# BRAIN.net
KiCad netlist of a schematic drawn in EAGLE
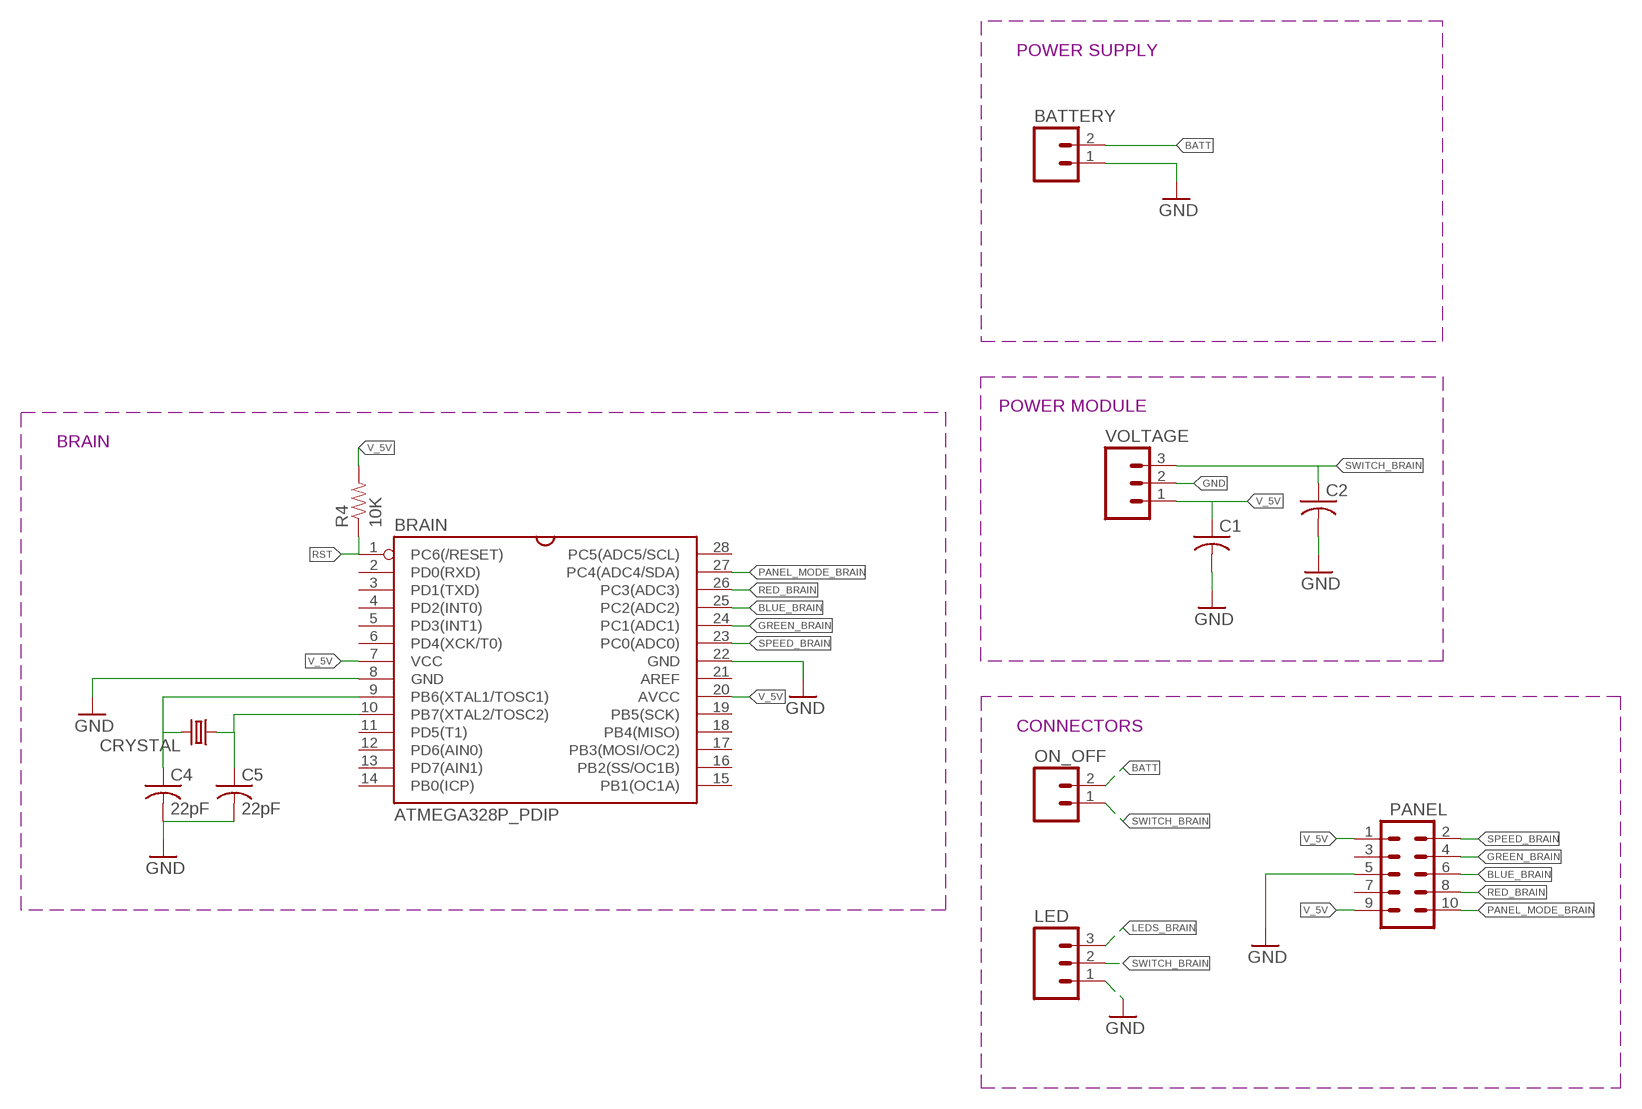
[diagram p0: schematic, sheet 1]

(export (version "E")
  (design (tool "Eeschema 10.0.6"))
  (components
    (comp (ref "BATTERY")
      (value "M02PTH")
      (footprint "eagle-import:1X02")
      (libsource (lib "eagle-import") (part "M02PTH"))
    )
    (comp (ref "BRAIN")
      (value "ATMEGA328P_PDIP")
      (footprint "eagle-import:DIL-28-3")
      (libsource (lib "eagle-import") (part "ATMEGA328P_PDIP"))
    )
    (comp (ref "C1")
      (value "C-US025-025X050")
      (footprint "eagle-import:C025-025X050")
      (libsource (lib "eagle-import") (part "C-US025-025X050"))
    )
    (comp (ref "C2")
      (value "C-US025-025X050")
      (footprint "eagle-import:C025-025X050")
      (libsource (lib "eagle-import") (part "C-US025-025X050"))
    )
    (comp (ref "C4")
      (value "22pF")
      (footprint "eagle-import:C025-024X044")
      (libsource (lib "eagle-import") (part "C-US025-024X044"))
    )
    (comp (ref "C5")
      (value "22pF")
      (footprint "eagle-import:C025-024X044")
      (libsource (lib "eagle-import") (part "C-US025-024X044"))
    )
    (comp (ref "CRYSTAL")
      (value "CRYSTALHC49US")
      (footprint "eagle-import:HC49US")
      (libsource (lib "eagle-import") (part "CRYSTALHC49US"))
    )
    (comp (ref "LED")
      (value "M03JST-PTH")
      (footprint "eagle-import:JST-3-PTH")
      (libsource (lib "eagle-import") (part "M03JST-PTH"))
    )
    (comp (ref "ON_OFF")
      (value "M02-JST-2-PTH-NO_SILK")
      (footprint "eagle-import:JST-2-PTH-NS")
      (libsource (lib "eagle-import") (part "M02-JST-2-PTH-NO_SILK"))
    )
    (comp (ref "PANEL")
      (value "M05X2SHD")
      (footprint "eagle-import:2X5-SHROUDED")
      (libsource (lib "eagle-import") (part "M05X2SHD"))
    )
    (comp (ref "R4")
      (value "10K")
      (footprint "eagle-import:1206")
      (libsource (lib "eagle-import") (part "RESISTOR1206"))
    )
    (comp (ref "VOLTAGE")
      (value "M03PTH")
      (footprint "eagle-import:1X03")
      (libsource (lib "eagle-import") (part "M03PTH"))
    )
  )
  (nets
    (net (code "1") (name "BATT") (class "Default")
      (node (ref "BATTERY") (pin "2") (pinfunction "2_2") (pintype "passive"))
      (node (ref "ON_OFF") (pin "2") (pinfunction "2_2") (pintype "passive"))
    )
    (net (code "2") (name "BLUE_BRAIN") (class "Default")
      (node (ref "BRAIN") (pin "25") (pinfunction "PC2(ADC2)_25") (pintype "bidirectional"))
      (node (ref "PANEL") (pin "6") (pinfunction "6_6") (pintype "passive"))
    )
    (net (code "3") (name "GND") (class "Default")
      (node (ref "BATTERY") (pin "1") (pinfunction "1_1") (pintype "passive"))
      (node (ref "BRAIN") (pin "22") (pinfunction "GND_22") (pintype "bidirectional"))
      (node (ref "BRAIN") (pin "8") (pinfunction "GND_8") (pintype "bidirectional"))
      (node (ref "C1") (pin "2") (pinfunction "2_2") (pintype "passive"))
      (node (ref "C2") (pin "2") (pinfunction "2_2") (pintype "passive"))
      (node (ref "C4") (pin "2") (pinfunction "2_2") (pintype "passive"))
      (node (ref "C5") (pin "2") (pinfunction "2_2") (pintype "passive"))
      (node (ref "LED") (pin "1") (pinfunction "1_1") (pintype "passive"))
      (node (ref "PANEL") (pin "5") (pinfunction "5_5") (pintype "passive"))
      (node (ref "VOLTAGE") (pin "2") (pinfunction "2_2") (pintype "passive"))
    )
    (net (code "4") (name "GREEN_BRAIN") (class "Default")
      (node (ref "BRAIN") (pin "24") (pinfunction "PC1(ADC1)_24") (pintype "bidirectional"))
      (node (ref "PANEL") (pin "4") (pinfunction "4_4") (pintype "passive"))
    )
    (net (code "5") (name "LEDS_BRAIN") (class "Default")
      (node (ref "LED") (pin "3") (pinfunction "3_3") (pintype "passive"))
    )
    (net (code "6") (name "Net-(BRAIN-PB6(XTAL1{slash}TOSC1))") (class "Default")
      (node (ref "BRAIN") (pin "9") (pinfunction "PB6(XTAL1/TOSC1)_9") (pintype "bidirectional"))
      (node (ref "C4") (pin "1") (pinfunction "1_1") (pintype "passive"))
      (node (ref "CRYSTAL") (pin "2") (pinfunction "2_2") (pintype "passive"))
    )
    (net (code "7") (name "Net-(BRAIN-PB7(XTAL2{slash}TOSC2))") (class "Default")
      (node (ref "BRAIN") (pin "10") (pinfunction "PB7(XTAL2/TOSC2)_10") (pintype "bidirectional"))
      (node (ref "C5") (pin "1") (pinfunction "1_1") (pintype "passive"))
      (node (ref "CRYSTAL") (pin "1") (pinfunction "1_1") (pintype "passive"))
    )
    (net (code "8") (name "PANEL_MODE_BRAIN") (class "Default")
      (node (ref "BRAIN") (pin "27") (pinfunction "PC4(ADC4/SDA)_27") (pintype "bidirectional"))
      (node (ref "PANEL") (pin "10") (pinfunction "10_10") (pintype "passive"))
    )
    (net (code "9") (name "RED_BRAIN") (class "Default")
      (node (ref "BRAIN") (pin "26") (pinfunction "PC3(ADC3)_26") (pintype "bidirectional"))
      (node (ref "PANEL") (pin "8") (pinfunction "8_8") (pintype "passive"))
    )
    (net (code "10") (name "RST") (class "Default")
      (node (ref "BRAIN") (pin "1") (pinfunction "PC6(/RESET)_1") (pintype "bidirectional"))
      (node (ref "R4") (pin "1") (pinfunction "1_1") (pintype "passive"))
    )
    (net (code "11") (name "SPEED_BRAIN") (class "Default")
      (node (ref "BRAIN") (pin "23") (pinfunction "PC0(ADC0)_23") (pintype "bidirectional"))
      (node (ref "PANEL") (pin "2") (pinfunction "2_2") (pintype "passive"))
    )
    (net (code "12") (name "SWITCH_BRAIN") (class "Default")
      (node (ref "C2") (pin "1") (pinfunction "1_1") (pintype "passive"))
      (node (ref "LED") (pin "2") (pinfunction "2_2") (pintype "passive"))
      (node (ref "ON_OFF") (pin "1") (pinfunction "1_1") (pintype "passive"))
      (node (ref "VOLTAGE") (pin "3") (pinfunction "3_3") (pintype "passive"))
    )
    (net (code "13") (name "V_5V") (class "Default")
      (node (ref "BRAIN") (pin "20") (pinfunction "AVCC_20") (pintype "bidirectional"))
      (node (ref "BRAIN") (pin "7") (pinfunction "VCC_7") (pintype "bidirectional"))
      (node (ref "C1") (pin "1") (pinfunction "1_1") (pintype "passive"))
      (node (ref "PANEL") (pin "1") (pinfunction "1_1") (pintype "passive"))
      (node (ref "PANEL") (pin "9") (pinfunction "9_9") (pintype "passive"))
      (node (ref "R4") (pin "2") (pinfunction "2_2") (pintype "passive"))
      (node (ref "VOLTAGE") (pin "1") (pinfunction "1_1") (pintype "passive"))
    )
    (net (code "14") (name "unconnected-(BRAIN-AREF-Pad21)") (class "Default")
      (node (ref "BRAIN") (pin "21") (pinfunction "AREF_21") (pintype "bidirectional"))
    )
    (net (code "15") (name "unconnected-(BRAIN-PB0(ICP)-Pad14)") (class "Default")
      (node (ref "BRAIN") (pin "14") (pinfunction "PB0(ICP)_14") (pintype "bidirectional"))
    )
    (net (code "16") (name "unconnected-(BRAIN-PB1(OC1A)-Pad15)") (class "Default")
      (node (ref "BRAIN") (pin "15") (pinfunction "PB1(OC1A)_15") (pintype "bidirectional"))
    )
    (net (code "17") (name "unconnected-(BRAIN-PB2(SS{slash}OC1B)-Pad16)") (class "Default")
      (node (ref "BRAIN") (pin "16") (pinfunction "PB2(SS/OC1B)_16") (pintype "bidirectional"))
    )
    (net (code "18") (name "unconnected-(BRAIN-PB3(MOSI{slash}OC2)-Pad17)") (class "Default")
      (node (ref "BRAIN") (pin "17") (pinfunction "PB3(MOSI/OC2)_17") (pintype "bidirectional"))
    )
    (net (code "19") (name "unconnected-(BRAIN-PB4(MISO)-Pad18)") (class "Default")
      (node (ref "BRAIN") (pin "18") (pinfunction "PB4(MISO)_18") (pintype "bidirectional"))
    )
    (net (code "20") (name "unconnected-(BRAIN-PB5(SCK)-Pad19)") (class "Default")
      (node (ref "BRAIN") (pin "19") (pinfunction "PB5(SCK)_19") (pintype "bidirectional"))
    )
    (net (code "21") (name "unconnected-(BRAIN-PC5(ADC5{slash}SCL)-Pad28)") (class "Default")
      (node (ref "BRAIN") (pin "28") (pinfunction "PC5(ADC5/SCL)_28") (pintype "bidirectional"))
    )
    (net (code "22") (name "unconnected-(BRAIN-PD0(RXD)-Pad2)") (class "Default")
      (node (ref "BRAIN") (pin "2") (pinfunction "PD0(RXD)_2") (pintype "bidirectional"))
    )
    (net (code "23") (name "unconnected-(BRAIN-PD1(TXD)-Pad3)") (class "Default")
      (node (ref "BRAIN") (pin "3") (pinfunction "PD1(TXD)_3") (pintype "bidirectional"))
    )
    (net (code "24") (name "unconnected-(BRAIN-PD2(INT0)-Pad4)") (class "Default")
      (node (ref "BRAIN") (pin "4") (pinfunction "PD2(INT0)_4") (pintype "bidirectional"))
    )
    (net (code "25") (name "unconnected-(BRAIN-PD3(INT1)-Pad5)") (class "Default")
      (node (ref "BRAIN") (pin "5") (pinfunction "PD3(INT1)_5") (pintype "bidirectional"))
    )
    (net (code "26") (name "unconnected-(BRAIN-PD4(XCK{slash}T0)-Pad6)") (class "Default")
      (node (ref "BRAIN") (pin "6") (pinfunction "PD4(XCK/T0)_6") (pintype "bidirectional"))
    )
    (net (code "27") (name "unconnected-(BRAIN-PD5(T1)-Pad11)") (class "Default")
      (node (ref "BRAIN") (pin "11") (pinfunction "PD5(T1)_11") (pintype "bidirectional"))
    )
    (net (code "28") (name "unconnected-(BRAIN-PD6(AIN0)-Pad12)") (class "Default")
      (node (ref "BRAIN") (pin "12") (pinfunction "PD6(AIN0)_12") (pintype "bidirectional"))
    )
    (net (code "29") (name "unconnected-(BRAIN-PD7(AIN1)-Pad13)") (class "Default")
      (node (ref "BRAIN") (pin "13") (pinfunction "PD7(AIN1)_13") (pintype "bidirectional"))
    )
    (net (code "30") (name "unconnected-(PANEL-Pad3)") (class "Default")
      (node (ref "PANEL") (pin "3") (pinfunction "3_3") (pintype "passive"))
    )
    (net (code "31") (name "unconnected-(PANEL-Pad7)") (class "Default")
      (node (ref "PANEL") (pin "7") (pinfunction "7_7") (pintype "passive"))
    )
  )
)
